# HandChip.net
KiCad netlist of a schematic drawn in Altium Designer
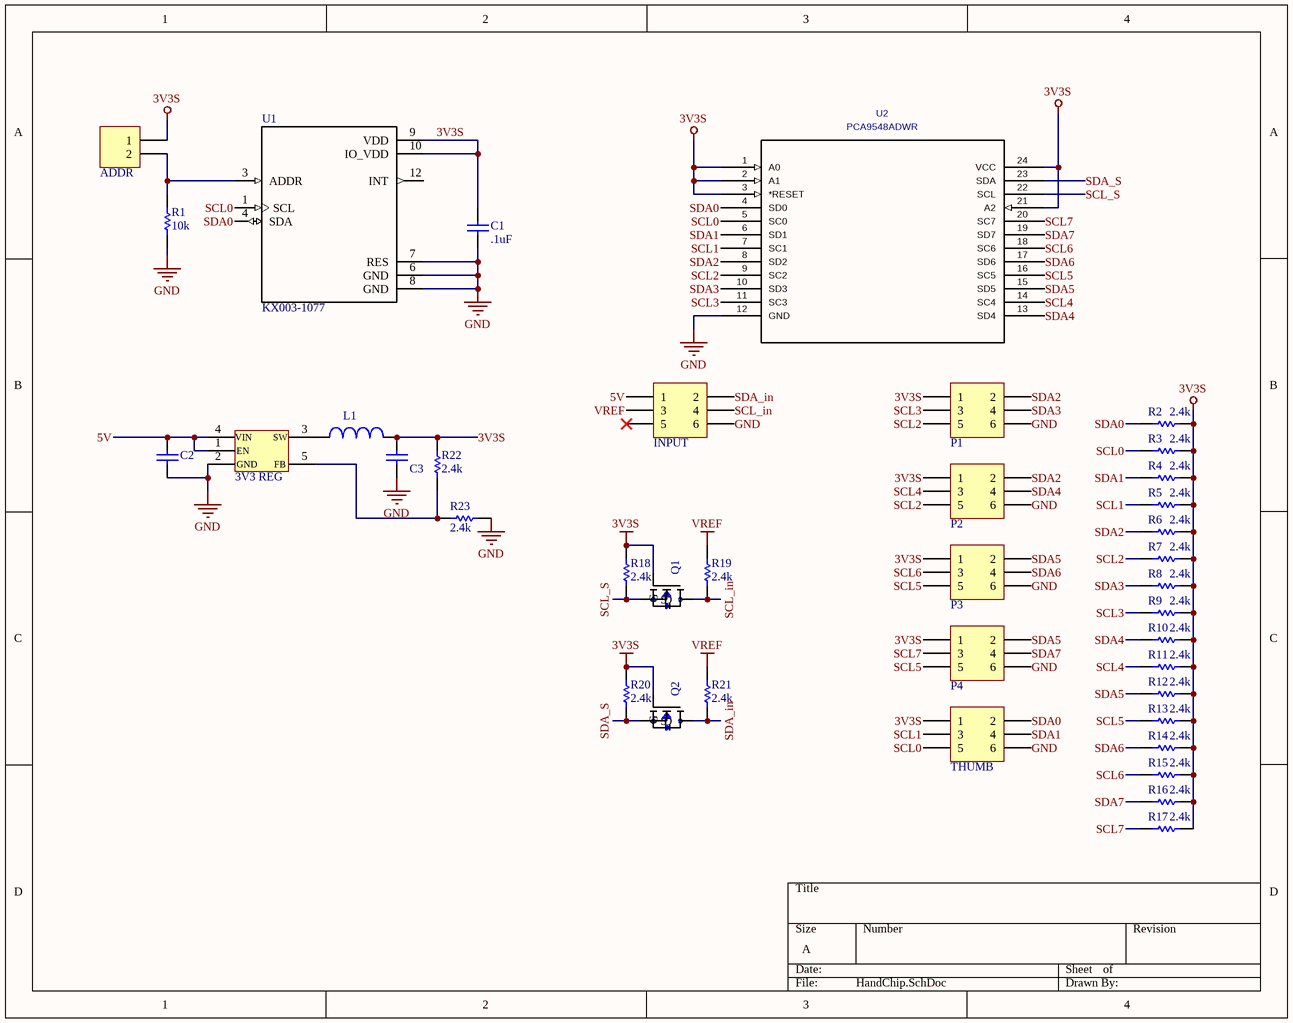
[diagram p0: HandChip.SchDoc]

(export (version "E")
  (design (tool "Eeschema 10.0.6"))
  (components
    (comp (ref "3V3 REG")
      (value "TLV62568DBVR")
      (footprint "*SOT95P280X145-5N")
      (libsource (lib "TLV62568DBVR") (part "TLV62568DBVR"))
    )
    (comp (ref "ADDR")
      (value "90120-0122")
      (footprint "HDR1X2")
      (description "MOLEX CONN HEADER 2POS .100\" STR TIN")
      (libsource (lib "AltiumGFU64") (part "Header 2"))
    )
    (comp (ref "C1")
      (value ".1uF")
      (footprint "0805-CAP")
      (description "Capacitor")
      (libsource (lib "Cap") (part "Cap"))
    )
    (comp (ref "C2")
      (value "Cap")
      (footprint "0805-CAP")
      (description "Capacitor")
      (libsource (lib "Cap") (part "Cap"))
    )
    (comp (ref "C3")
      (value "Cap")
      (footprint "0805-CAP")
      (description "Capacitor")
      (libsource (lib "Cap") (part "Cap"))
    )
    (comp (ref "INPUT")
      (value "90131-0123")
      (footprint "HDR2X3")
      (description "MOLEX CONN HEADER 6POS 2ROW .100\" STR TIN")
      (libsource (lib "AltiumGFU64") (part "Header 3X2"))
    )
    (comp (ref "L1")
      (value "SDR0403-2R2ML")
      (footprint "*SDR0403")
      (description "2.2µH Unshielded Wirewound Inductor 2.6A 47mOhm Max Nonstandard")
      (fields (field (name "MF") "Bourns"))
      (libsource (lib "SDR0403-2R2ML") (part "SDR0403-2R2ML"))
    )
    (comp (ref "P1")
      (value "90131-0123")
      (footprint "HDR2X3")
      (description "MOLEX CONN HEADER 6POS 2ROW .100\" STR TIN")
      (libsource (lib "AltiumGFU64") (part "Header 3X2"))
    )
    (comp (ref "P2")
      (value "90131-0123")
      (footprint "HDR2X3")
      (description "MOLEX CONN HEADER 6POS 2ROW .100\" STR TIN")
      (libsource (lib "AltiumGFU64") (part "Header 3X2"))
    )
    (comp (ref "P3")
      (value "90131-0123")
      (footprint "HDR2X3")
      (description "MOLEX CONN HEADER 6POS 2ROW .100\" STR TIN")
      (libsource (lib "AltiumGFU64") (part "Header 3X2"))
    )
    (comp (ref "P4")
      (value "90131-0123")
      (footprint "HDR2X3")
      (description "MOLEX CONN HEADER 6POS 2ROW .100\" STR TIN")
      (libsource (lib "AltiumGFU64") (part "Header 3X2"))
    )
    (comp (ref "Q1")
      (value "BSS138")
      (footprint "*BSS138_BSS138(Primary)")
      (description "N-Channel 50V 220mA _Ta_ 360mW _Ta_ Surface Mount Die")
      (fields (field (name "MF") "MICROSS/On Semiconductor"))
      (libsource (lib "BSS138") (part "BSS138"))
    )
    (comp (ref "Q2")
      (value "BSS138")
      (footprint "*BSS138_BSS138(Primary)")
      (description "N-Channel 50V 220mA _Ta_ 360mW _Ta_ Surface Mount Die")
      (fields (field (name "MF") "MICROSS/On Semiconductor"))
      (libsource (lib "BSS138") (part "BSS138"))
    )
    (comp (ref "R1")
      (value "10k")
      (footprint "0805-RES")
      (description "Resistor")
      (libsource (lib "ResBasic") (part "ResBasic"))
    )
    (comp (ref "R2")
      (value "2.4k")
      (footprint "0805-RES")
      (description "Resistor")
      (libsource (lib "ResBasic") (part "ResBasic"))
    )
    (comp (ref "R3")
      (value "2.4k")
      (footprint "0805-RES")
      (description "Resistor")
      (libsource (lib "ResBasic") (part "ResBasic"))
    )
    (comp (ref "R4")
      (value "2.4k")
      (footprint "0805-RES")
      (description "Resistor")
      (libsource (lib "ResBasic") (part "ResBasic"))
    )
    (comp (ref "R5")
      (value "2.4k")
      (footprint "0805-RES")
      (description "Resistor")
      (libsource (lib "ResBasic") (part "ResBasic"))
    )
    (comp (ref "R6")
      (value "2.4k")
      (footprint "0805-RES")
      (description "Resistor")
      (libsource (lib "ResBasic") (part "ResBasic"))
    )
    (comp (ref "R7")
      (value "2.4k")
      (footprint "0805-RES")
      (description "Resistor")
      (libsource (lib "ResBasic") (part "ResBasic"))
    )
    (comp (ref "R8")
      (value "2.4k")
      (footprint "0805-RES")
      (description "Resistor")
      (libsource (lib "ResBasic") (part "ResBasic"))
    )
    (comp (ref "R9")
      (value "2.4k")
      (footprint "0805-RES")
      (description "Resistor")
      (libsource (lib "ResBasic") (part "ResBasic"))
    )
    (comp (ref "R10")
      (value "2.4k")
      (footprint "0805-RES")
      (description "Resistor")
      (libsource (lib "ResBasic") (part "ResBasic"))
    )
    (comp (ref "R11")
      (value "2.4k")
      (footprint "0805-RES")
      (description "Resistor")
      (libsource (lib "ResBasic") (part "ResBasic"))
    )
    (comp (ref "R12")
      (value "2.4k")
      (footprint "0805-RES")
      (description "Resistor")
      (libsource (lib "ResBasic") (part "ResBasic"))
    )
    (comp (ref "R13")
      (value "2.4k")
      (footprint "0805-RES")
      (description "Resistor")
      (libsource (lib "ResBasic") (part "ResBasic"))
    )
    (comp (ref "R14")
      (value "2.4k")
      (footprint "0805-RES")
      (description "Resistor")
      (libsource (lib "ResBasic") (part "ResBasic"))
    )
    (comp (ref "R15")
      (value "2.4k")
      (footprint "0805-RES")
      (description "Resistor")
      (libsource (lib "ResBasic") (part "ResBasic"))
    )
    (comp (ref "R16")
      (value "2.4k")
      (footprint "0805-RES")
      (description "Resistor")
      (libsource (lib "ResBasic") (part "ResBasic"))
    )
    (comp (ref "R17")
      (value "2.4k")
      (footprint "0805-RES")
      (description "Resistor")
      (libsource (lib "ResBasic") (part "ResBasic"))
    )
    (comp (ref "R18")
      (value "2.4k")
      (footprint "0805-RES")
      (description "Resistor")
      (libsource (lib "ResBasic") (part "ResBasic"))
    )
    (comp (ref "R19")
      (value "2.4k")
      (footprint "0805-RES")
      (description "Resistor")
      (libsource (lib "ResBasic") (part "ResBasic"))
    )
    (comp (ref "R20")
      (value "2.4k")
      (footprint "0805-RES")
      (description "Resistor")
      (libsource (lib "ResBasic") (part "ResBasic"))
    )
    (comp (ref "R21")
      (value "2.4k")
      (footprint "0805-RES")
      (description "Resistor")
      (libsource (lib "ResBasic") (part "ResBasic"))
    )
    (comp (ref "R22")
      (value "2.4k")
      (footprint "0805-RES")
      (description "Resistor")
      (libsource (lib "ResBasic") (part "ResBasic"))
    )
    (comp (ref "R23")
      (value "2.4k")
      (footprint "0805-RES")
      (description "Resistor")
      (libsource (lib "ResBasic") (part "ResBasic"))
    )
    (comp (ref "THUMB")
      (value "90131-0123")
      (footprint "HDR2X3")
      (description "MOLEX CONN HEADER 6POS 2ROW .100\" STR TIN")
      (libsource (lib "AltiumGFU64") (part "Header 3X2"))
    )
    (comp (ref "U1")
      (value "KX003-1077")
      (footprint "*XDCR_KX003-1077")
      (description "Accelerometer X, Y, Z Axis Â±2g, 4g, 8g, 16g 3.5kHz _X,Y_, 1.8kHz _Z_ 12-LGA _2x2_")
      (fields
        (field (name "DIGI-KEY_PART_NUMBER") "KX003-1077CT-ND")
        (field (name "MF") "Rohm Semiconductor")
      )
      (libsource (lib "KX003-1077") (part "KX003-1077"))
    )
    (comp (ref "U2")
      (value "PCA9548ADWR")
      (footprint "DW24")
      (fields (field (name "MANUFACTURER") "Texas Instruments"))
      (libsource (lib "I2C_MUX") (part "PCA9548ADWR"))
    )
  )
  (nets
    (net (code "1") (name "/5V") (class "Default")
      (node (ref "3V3 REG") (pin "1") (pinfunction "1_1") (pintype "passive"))
      (node (ref "3V3 REG") (pin "4") (pinfunction "4_4") (pintype "passive"))
      (node (ref "C2") (pin "2") (pinfunction "2_2") (pintype "passive"))
      (node (ref "INPUT") (pin "1") (pinfunction "1_1") (pintype "passive"))
    )
    (net (code "2") (name "/SCL0") (class "Default")
      (node (ref "R3") (pin "2") (pinfunction "2_2") (pintype "passive"))
      (node (ref "THUMB") (pin "5") (pinfunction "5_5") (pintype "passive"))
      (node (ref "U1") (pin "1") (pinfunction "SCL_1") (pintype "input"))
      (node (ref "U2") (pin "5") (pinfunction "SC0_5") (pintype "passive"))
    )
    (net (code "3") (name "/SCL1") (class "Default")
      (node (ref "R5") (pin "2") (pinfunction "2_2") (pintype "passive"))
      (node (ref "THUMB") (pin "3") (pinfunction "3_3") (pintype "passive"))
      (node (ref "U2") (pin "7") (pinfunction "SC1_7") (pintype "passive"))
    )
    (net (code "4") (name "/SCL2") (class "Default")
      (node (ref "P1") (pin "5") (pinfunction "5_5") (pintype "passive"))
      (node (ref "P2") (pin "5") (pinfunction "5_5") (pintype "passive"))
      (node (ref "R7") (pin "2") (pinfunction "2_2") (pintype "passive"))
      (node (ref "U2") (pin "9") (pinfunction "SC2_9") (pintype "passive"))
    )
    (net (code "5") (name "/SCL3") (class "Default")
      (node (ref "P1") (pin "3") (pinfunction "3_3") (pintype "passive"))
      (node (ref "R9") (pin "2") (pinfunction "2_2") (pintype "passive"))
      (node (ref "U2") (pin "11") (pinfunction "SC3_11") (pintype "passive"))
    )
    (net (code "6") (name "/SCL4") (class "Default")
      (node (ref "P2") (pin "3") (pinfunction "3_3") (pintype "passive"))
      (node (ref "R11") (pin "2") (pinfunction "2_2") (pintype "passive"))
      (node (ref "U2") (pin "14") (pinfunction "SC4_14") (pintype "passive"))
    )
    (net (code "7") (name "/SCL5") (class "Default")
      (node (ref "P3") (pin "5") (pinfunction "5_5") (pintype "passive"))
      (node (ref "P4") (pin "5") (pinfunction "5_5") (pintype "passive"))
      (node (ref "R13") (pin "2") (pinfunction "2_2") (pintype "passive"))
      (node (ref "U2") (pin "16") (pinfunction "SC5_16") (pintype "passive"))
    )
    (net (code "8") (name "/SCL6") (class "Default")
      (node (ref "P3") (pin "3") (pinfunction "3_3") (pintype "passive"))
      (node (ref "R15") (pin "2") (pinfunction "2_2") (pintype "passive"))
      (node (ref "U2") (pin "18") (pinfunction "SC6_18") (pintype "passive"))
    )
    (net (code "9") (name "/SCL7") (class "Default")
      (node (ref "P4") (pin "3") (pinfunction "3_3") (pintype "passive"))
      (node (ref "R17") (pin "2") (pinfunction "2_2") (pintype "passive"))
      (node (ref "U2") (pin "20") (pinfunction "SC7_20") (pintype "passive"))
    )
    (net (code "10") (name "/SCL_S") (class "Default")
      (node (ref "Q1") (pin "S") (pinfunction "S_S") (pintype "passive"))
      (node (ref "R18") (pin "2") (pinfunction "2_2") (pintype "passive"))
      (node (ref "U2") (pin "22") (pinfunction "SCL_22") (pintype "passive"))
    )
    (net (code "11") (name "/SCL_in") (class "Default")
      (node (ref "INPUT") (pin "4") (pinfunction "4_4") (pintype "passive"))
      (node (ref "Q1") (pin "D") (pinfunction "D_D") (pintype "passive"))
      (node (ref "R19") (pin "2") (pinfunction "2_2") (pintype "passive"))
    )
    (net (code "12") (name "/SDA0") (class "Default")
      (node (ref "R2") (pin "2") (pinfunction "2_2") (pintype "passive"))
      (node (ref "THUMB") (pin "2") (pinfunction "2_2") (pintype "passive"))
      (node (ref "U1") (pin "4") (pinfunction "SDA_4") (pintype "bidirectional"))
      (node (ref "U2") (pin "4") (pinfunction "SD0_4") (pintype "passive"))
    )
    (net (code "13") (name "/SDA1") (class "Default")
      (node (ref "R4") (pin "2") (pinfunction "2_2") (pintype "passive"))
      (node (ref "THUMB") (pin "4") (pinfunction "4_4") (pintype "passive"))
      (node (ref "U2") (pin "6") (pinfunction "SD1_6") (pintype "passive"))
    )
    (net (code "14") (name "/SDA2") (class "Default")
      (node (ref "P1") (pin "2") (pinfunction "2_2") (pintype "passive"))
      (node (ref "P2") (pin "2") (pinfunction "2_2") (pintype "passive"))
      (node (ref "R6") (pin "2") (pinfunction "2_2") (pintype "passive"))
      (node (ref "U2") (pin "8") (pinfunction "SD2_8") (pintype "passive"))
    )
    (net (code "15") (name "/SDA3") (class "Default")
      (node (ref "P1") (pin "4") (pinfunction "4_4") (pintype "passive"))
      (node (ref "R8") (pin "2") (pinfunction "2_2") (pintype "passive"))
      (node (ref "U2") (pin "10") (pinfunction "SD3_10") (pintype "passive"))
    )
    (net (code "16") (name "/SDA4") (class "Default")
      (node (ref "P2") (pin "4") (pinfunction "4_4") (pintype "passive"))
      (node (ref "R10") (pin "2") (pinfunction "2_2") (pintype "passive"))
      (node (ref "U2") (pin "13") (pinfunction "SD4_13") (pintype "passive"))
    )
    (net (code "17") (name "/SDA5") (class "Default")
      (node (ref "P3") (pin "2") (pinfunction "2_2") (pintype "passive"))
      (node (ref "P4") (pin "2") (pinfunction "2_2") (pintype "passive"))
      (node (ref "R12") (pin "2") (pinfunction "2_2") (pintype "passive"))
      (node (ref "U2") (pin "15") (pinfunction "SD5_15") (pintype "passive"))
    )
    (net (code "18") (name "/SDA6") (class "Default")
      (node (ref "P3") (pin "4") (pinfunction "4_4") (pintype "passive"))
      (node (ref "R14") (pin "2") (pinfunction "2_2") (pintype "passive"))
      (node (ref "U2") (pin "17") (pinfunction "SD6_17") (pintype "passive"))
    )
    (net (code "19") (name "/SDA7") (class "Default")
      (node (ref "P4") (pin "4") (pinfunction "4_4") (pintype "passive"))
      (node (ref "R16") (pin "2") (pinfunction "2_2") (pintype "passive"))
      (node (ref "U2") (pin "19") (pinfunction "SD7_19") (pintype "passive"))
    )
    (net (code "20") (name "/SDA_S") (class "Default")
      (node (ref "Q2") (pin "S") (pinfunction "S_S") (pintype "passive"))
      (node (ref "R20") (pin "2") (pinfunction "2_2") (pintype "passive"))
      (node (ref "U2") (pin "23") (pinfunction "SDA_23") (pintype "passive"))
    )
    (net (code "21") (name "/SDA_in") (class "Default")
      (node (ref "INPUT") (pin "2") (pinfunction "2_2") (pintype "passive"))
      (node (ref "Q2") (pin "D") (pinfunction "D_D") (pintype "passive"))
      (node (ref "R21") (pin "2") (pinfunction "2_2") (pintype "passive"))
    )
    (net (code "22") (name "3V3S") (class "Default")
      (node (ref "ADDR") (pin "1") (pinfunction "1_1") (pintype "passive"))
      (node (ref "C1") (pin "2") (pinfunction "2_2") (pintype "passive"))
      (node (ref "C3") (pin "2") (pinfunction "2_2") (pintype "passive"))
      (node (ref "L1") (pin "2") (pinfunction "2_2") (pintype "passive"))
      (node (ref "P1") (pin "1") (pinfunction "1_1") (pintype "passive"))
      (node (ref "P2") (pin "1") (pinfunction "1_1") (pintype "passive"))
      (node (ref "P3") (pin "1") (pinfunction "1_1") (pintype "passive"))
      (node (ref "P4") (pin "1") (pinfunction "1_1") (pintype "passive"))
      (node (ref "Q1") (pin "G") (pinfunction "G_G") (pintype "passive"))
      (node (ref "Q2") (pin "G") (pinfunction "G_G") (pintype "passive"))
      (node (ref "R10") (pin "1") (pinfunction "1_1") (pintype "passive"))
      (node (ref "R11") (pin "1") (pinfunction "1_1") (pintype "passive"))
      (node (ref "R12") (pin "1") (pinfunction "1_1") (pintype "passive"))
      (node (ref "R13") (pin "1") (pinfunction "1_1") (pintype "passive"))
      (node (ref "R14") (pin "1") (pinfunction "1_1") (pintype "passive"))
      (node (ref "R15") (pin "1") (pinfunction "1_1") (pintype "passive"))
      (node (ref "R16") (pin "1") (pinfunction "1_1") (pintype "passive"))
      (node (ref "R17") (pin "1") (pinfunction "1_1") (pintype "passive"))
      (node (ref "R18") (pin "1") (pinfunction "1_1") (pintype "passive"))
      (node (ref "R2") (pin "1") (pinfunction "1_1") (pintype "passive"))
      (node (ref "R20") (pin "1") (pinfunction "1_1") (pintype "passive"))
      (node (ref "R22") (pin "1") (pinfunction "1_1") (pintype "passive"))
      (node (ref "R3") (pin "1") (pinfunction "1_1") (pintype "passive"))
      (node (ref "R4") (pin "1") (pinfunction "1_1") (pintype "passive"))
      (node (ref "R5") (pin "1") (pinfunction "1_1") (pintype "passive"))
      (node (ref "R6") (pin "1") (pinfunction "1_1") (pintype "passive"))
      (node (ref "R7") (pin "1") (pinfunction "1_1") (pintype "passive"))
      (node (ref "R8") (pin "1") (pinfunction "1_1") (pintype "passive"))
      (node (ref "R9") (pin "1") (pinfunction "1_1") (pintype "passive"))
      (node (ref "THUMB") (pin "1") (pinfunction "1_1") (pintype "passive"))
      (node (ref "U1") (pin "10") (pinfunction "IO_VDD_10") (pintype "power_in"))
      (node (ref "U1") (pin "9") (pinfunction "VDD_9") (pintype "power_in"))
      (node (ref "U2") (pin "1") (pinfunction "A0_1") (pintype "input"))
      (node (ref "U2") (pin "2") (pinfunction "A1_2") (pintype "input"))
      (node (ref "U2") (pin "21") (pinfunction "A2_21") (pintype "input"))
      (node (ref "U2") (pin "24") (pinfunction "VCC_24") (pintype "power_in"))
      (node (ref "U2") (pin "3") (pinfunction "*RESET_3") (pintype "input"))
    )
    (net (code "23") (name "GND") (class "Default")
      (node (ref "3V3 REG") (pin "2") (pinfunction "2_2") (pintype "passive"))
      (node (ref "C1") (pin "1") (pinfunction "1_1") (pintype "passive"))
      (node (ref "C2") (pin "1") (pinfunction "1_1") (pintype "passive"))
      (node (ref "C3") (pin "1") (pinfunction "1_1") (pintype "passive"))
      (node (ref "INPUT") (pin "6") (pinfunction "6_6") (pintype "passive"))
      (node (ref "P1") (pin "6") (pinfunction "6_6") (pintype "passive"))
      (node (ref "P2") (pin "6") (pinfunction "6_6") (pintype "passive"))
      (node (ref "P3") (pin "6") (pinfunction "6_6") (pintype "passive"))
      (node (ref "P4") (pin "6") (pinfunction "6_6") (pintype "passive"))
      (node (ref "R1") (pin "1") (pinfunction "1_1") (pintype "passive"))
      (node (ref "R23") (pin "2") (pinfunction "2_2") (pintype "passive"))
      (node (ref "THUMB") (pin "6") (pinfunction "6_6") (pintype "passive"))
      (node (ref "U1") (pin "6") (pinfunction "GND_6") (pintype "power_in"))
      (node (ref "U1") (pin "7") (pinfunction "RES_7") (pintype "power_in"))
      (node (ref "U1") (pin "8") (pinfunction "GND_8") (pintype "power_in"))
      (node (ref "U2") (pin "12") (pinfunction "GND_12") (pintype "power_in"))
    )
    (net (code "24") (name "Net-(3V3 REG-Pad3)") (class "Default")
      (node (ref "3V3 REG") (pin "3") (pinfunction "3_3") (pintype "passive"))
      (node (ref "L1") (pin "1") (pinfunction "1_1") (pintype "passive"))
    )
    (net (code "25") (name "Net-(3V3 REG-Pad5)") (class "Default")
      (node (ref "3V3 REG") (pin "5") (pinfunction "5_5") (pintype "passive"))
      (node (ref "R22") (pin "2") (pinfunction "2_2") (pintype "passive"))
      (node (ref "R23") (pin "1") (pinfunction "1_1") (pintype "passive"))
    )
    (net (code "26") (name "Net-(U1-ADDR)") (class "Default")
      (node (ref "ADDR") (pin "2") (pinfunction "2_2") (pintype "passive"))
      (node (ref "R1") (pin "2") (pinfunction "2_2") (pintype "passive"))
      (node (ref "U1") (pin "3") (pinfunction "ADDR_3") (pintype "input"))
    )
    (net (code "27") (name "VREF") (class "Default")
      (node (ref "INPUT") (pin "3") (pinfunction "3_3") (pintype "passive"))
      (node (ref "R19") (pin "1") (pinfunction "1_1") (pintype "passive"))
      (node (ref "R21") (pin "1") (pinfunction "1_1") (pintype "passive"))
    )
    (net (code "28") (name "unconnected-(INPUT-Pad5)") (class "Default")
      (node (ref "INPUT") (pin "5") (pinfunction "5_5") (pintype "passive+no_connect"))
    )
    (net (code "29") (name "unconnected-(U1-INT-Pad12)") (class "Default")
      (node (ref "U1") (pin "12") (pinfunction "INT_12") (pintype "output"))
    )
  )
)
